# DriverControls_PeripheralMain.net
KiCad netlist of a schematic drawn in Altium Designer
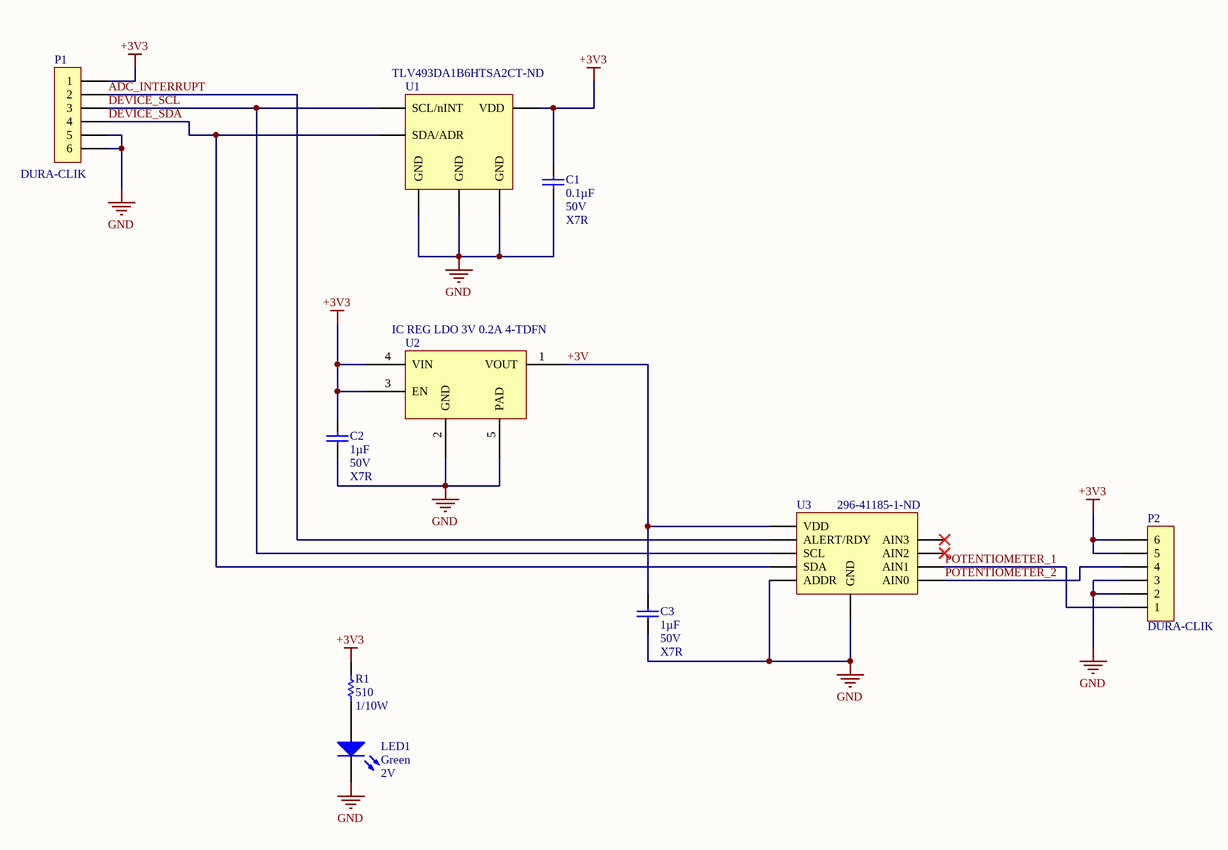
[diagram p0: DriverControls_PeripheralMain.SchDoc]

(export (version "E")
  (design (tool "Eeschema 10.0.6"))
  (components
    (comp (ref "C1")
      (value "CAP CER 0.1UF 50V 10% X7R 0603")
      (footprint "CAP, 0603")
      (description "0.10µF ±10% 50V Ceramic Capacitor X7R 0603 (1608 Metric)")
      (fields
        (field (name "TOLERANCE") "±10%")
        (field (name "CAPACITANCE") "0.1µF")
        (field (name "VOLTAGE") "50V")
        (field (name "TEMPERATURE COEFFICIENT") "X7R")
      )
      (libsource (lib "Schematic Diagrams") (part "CAP CER 0.1UF 50V 10% X7R 0603"))
    )
    (comp (ref "C2")
      (value "CAP CER 1UF 50V 10% X7R 0603")
      (footprint "CAP, 0603")
      (description "1µF ±10% 50V Ceramic Capacitor X7R 0603 (1608 Metric)")
      (fields
        (field (name "TOLERANCE") "±10%")
        (field (name "CAPACITANCE") "1µF")
        (field (name "VOLTAGE") "50V")
        (field (name "TEMPERATURE COEFFICIENT") "X7R")
      )
      (libsource (lib "Schematic Diagrams") (part "CAP CER 1UF 50V 10% X7R 0603"))
    )
    (comp (ref "C3")
      (value "CAP CER 1UF 50V 10% X7R 0603")
      (footprint "CAP, 0603")
      (description "1µF ±10% 50V Ceramic Capacitor X7R 0603 (1608 Metric)")
      (fields
        (field (name "TOLERANCE") "±10%")
        (field (name "CAPACITANCE") "1µF")
        (field (name "VOLTAGE") "50V")
        (field (name "TEMPERATURE COEFFICIENT") "X7R")
      )
      (libsource (lib "Schematic Diagrams") (part "CAP CER 1UF 50V 10% X7R 0603"))
    )
    (comp (ref "LED1")
      (value "LED GREEN CLEAR 2V 0603")
      (footprint "LED_0603")
      (description "Green 572nm LED Indication - Discrete 2V 0603 (1608 Metric)")
      (fields
        (field (name "MANUFACTURER") "Wurth Electronics Inc.")
        (field (name "MANUFACTURER PART NUMBER") "150060VS75000")
        (field (name "COLOR") "Green")
        (field (name "VOLTAGE - FORWARD (VF) (TYP)") "2V")
      )
      (libsource (lib "Schematic Diagrams") (part "LED GREEN CLEAR 2V 0603"))
    )
    (comp (ref "P1")
      (value "DURA-CLIK")
      (footprint "CONN, 6POS DURA-CLIK VERT")
      (description "6 Positions Header, Shrouded Connector 0.079\" (2.00mm) Surface Mount, Vertical Tin")
      (fields (field (name "MANUFACTURER") "Molex") (field (name "MANUFACTURER PART NUMBER") "5600200820"))
      (libsource (lib "Schematic Diagrams") (part "CONN 6POS DURA-CLIK 0.079{dblquote}"))
    )
    (comp (ref "P2")
      (value "DURA-CLIK")
      (footprint "CONN, 6POS DURA-CLIK VERT")
      (description "6 Positions Header, Shrouded Connector 0.079\" (2.00mm) Surface Mount, Vertical Tin")
      (fields (field (name "MANUFACTURER") "Molex") (field (name "MANUFACTURER PART NUMBER") "5600200820"))
      (libsource (lib "") (part "CONN 6POS DURA-CLIK 0.079{dblquote}_1"))
    )
    (comp (ref "R1")
      (value "RES 510 OHM 5% 1/10W 0603")
      (footprint "RES, 0603")
      (description "RES SMD 510 OHM 5% 1/10W 0603")
      (fields
        (field (name "TOLERANCE") "±5%")
        (field (name "RESISTANCE") "510")
        (field (name "POWER") "1/10W")
      )
      (libsource (lib "Schematic Diagrams") (part "RES 510 OHM 5% 1/10W 0603"))
    )
    (comp (ref "U1")
      (value "HALL EFFECT")
      (footprint "IC TLV496D MAG SENSOR TSOP-6")
      (description "Hall Effect Sensor Linear, Rotary Position External Magnet Not Included SMD (SMT) Tab")
      (fields
        (field (name "MANUFACTURER") "Infineon Technologies")
        (field (name "MANUFACTURER PART NUMBER") "TLV493DA1B6HTSA2")
        (field (name "SUPPLIER PART NUMBER 1") "TLV493DA1B6HTSA2CT-ND")
      )
      (libsource (lib "Schematic Diagrams") (part "IC SENSOR HALL I2C TSOP-6"))
    )
    (comp (ref "U2")
      (value "IC REG LDO 3V 0.2A 4-TDFN")
      (footprint "IC REG LDO 3V 0.2A 4-TDFN")
      (fields
        (field (name "MANUFACTURER") "Microchip Technology")
        (field (name "MANUFACTURER PART NUMBER") "MIC94310-PYMT-TR")
      )
      (libsource (lib "Schematic Diagrams") (part "IC REG LDO 3V 0.2A 4-TDFN"))
    )
    (comp (ref "U3")
      (value "Quad ADC")
      (footprint "IC ADC VSSOP10")
      (description "12 Bit Analog to Digital Converter 4 Input 1 Sigma-Delta 10-VSSOP")
      (fields
        (field (name "MANUFACTURER") "Texas Instruments")
        (field (name "MANUFACTURER PART NUMBER") "ADS1015IDGSR")
        (field (name "SUPPLIER PART NUMBER 1") "296-41185-1-ND")
      )
      (libsource (lib "Schematic Diagrams") (part "IC ADC 12-BIT VSSOP-10"))
    )
  )
  (nets
    (net (code "1") (name "+3V3") (class "Default")
      (node (ref "C1") (pin "1") (pinfunction "1_1") (pintype "passive"))
      (node (ref "C2") (pin "1") (pinfunction "1_1") (pintype "passive"))
      (node (ref "P1") (pin "1") (pinfunction "1_1") (pintype "passive"))
      (node (ref "P2") (pin "5") (pinfunction "5_5") (pintype "passive"))
      (node (ref "P2") (pin "6") (pinfunction "6_6") (pintype "passive"))
      (node (ref "R1") (pin "1") (pinfunction "1_1") (pintype "passive"))
      (node (ref "U1") (pin "4") (pinfunction "VDD_4") (pintype "passive"))
      (node (ref "U2") (pin "3") (pinfunction "EN_3") (pintype "passive"))
      (node (ref "U2") (pin "4") (pinfunction "VIN_4") (pintype "passive"))
    )
    (net (code "2") (name "/+3V") (class "Default")
      (node (ref "C3") (pin "1") (pinfunction "1_1") (pintype "passive"))
      (node (ref "U2") (pin "1") (pinfunction "VOUT_1") (pintype "passive"))
      (node (ref "U3") (pin "8") (pinfunction "VDD_8") (pintype "passive"))
    )
    (net (code "3") (name "/ADC_INTERRUPT") (class "Default")
      (node (ref "P1") (pin "2") (pinfunction "2_2") (pintype "passive"))
      (node (ref "U3") (pin "2") (pinfunction "ALERT/RDY_2") (pintype "passive"))
    )
    (net (code "4") (name "/DEVICE_SCL") (class "Default")
      (node (ref "P1") (pin "3") (pinfunction "3_3") (pintype "passive"))
      (node (ref "U1") (pin "1") (pinfunction "SCL/nINT_1") (pintype "passive"))
      (node (ref "U3") (pin "10") (pinfunction "SCL_10") (pintype "passive"))
    )
    (net (code "5") (name "/DEVICE_SDA") (class "Default")
      (node (ref "P1") (pin "4") (pinfunction "4_4") (pintype "passive"))
      (node (ref "U1") (pin "6") (pinfunction "SDA/ADR_6") (pintype "passive"))
      (node (ref "U3") (pin "9") (pinfunction "SDA_9") (pintype "passive"))
    )
    (net (code "6") (name "/POTENTIOMETER_1") (class "Default")
      (node (ref "P2") (pin "1") (pinfunction "1_1") (pintype "passive"))
      (node (ref "U3") (pin "5") (pinfunction "AIN1_5") (pintype "passive"))
    )
    (net (code "7") (name "/POTENTIOMETER_2") (class "Default")
      (node (ref "P2") (pin "4") (pinfunction "4_4") (pintype "passive"))
      (node (ref "U3") (pin "4") (pinfunction "AIN0_4") (pintype "passive"))
    )
    (net (code "8") (name "GND") (class "Default")
      (node (ref "C1") (pin "2") (pinfunction "2_2") (pintype "passive"))
      (node (ref "C2") (pin "2") (pinfunction "2_2") (pintype "passive"))
      (node (ref "C3") (pin "2") (pinfunction "2_2") (pintype "passive"))
      (node (ref "LED1") (pin "2") (pinfunction "K_2") (pintype "passive"))
      (node (ref "P1") (pin "5") (pinfunction "5_5") (pintype "passive"))
      (node (ref "P1") (pin "6") (pinfunction "6_6") (pintype "passive"))
      (node (ref "P2") (pin "2") (pinfunction "2_2") (pintype "passive"))
      (node (ref "P2") (pin "3") (pinfunction "3_3") (pintype "passive"))
      (node (ref "U1") (pin "2") (pinfunction "GND_2") (pintype "passive"))
      (node (ref "U1") (pin "3") (pinfunction "GND_3") (pintype "passive"))
      (node (ref "U1") (pin "5") (pinfunction "GND_5") (pintype "passive"))
      (node (ref "U2") (pin "2") (pinfunction "GND_2") (pintype "passive"))
      (node (ref "U2") (pin "5") (pinfunction "PAD_5") (pintype "passive"))
      (node (ref "U3") (pin "1") (pinfunction "ADDR_1") (pintype "passive"))
      (node (ref "U3") (pin "3") (pinfunction "GND_3") (pintype "passive"))
    )
    (net (code "9") (name "Net-(LED1-A)") (class "Default")
      (node (ref "LED1") (pin "1") (pinfunction "A_1") (pintype "passive"))
      (node (ref "R1") (pin "2") (pinfunction "2_2") (pintype "passive"))
    )
    (net (code "10") (name "unconnected-(U3-AIN2-Pad6)") (class "Default")
      (node (ref "U3") (pin "6") (pinfunction "AIN2_6") (pintype "passive+no_connect"))
    )
    (net (code "11") (name "unconnected-(U3-AIN3-Pad7)") (class "Default")
      (node (ref "U3") (pin "7") (pinfunction "AIN3_7") (pintype "passive+no_connect"))
    )
  )
)
